# meduZa.net
KiCad netlist of a schematic drawn in EAGLE
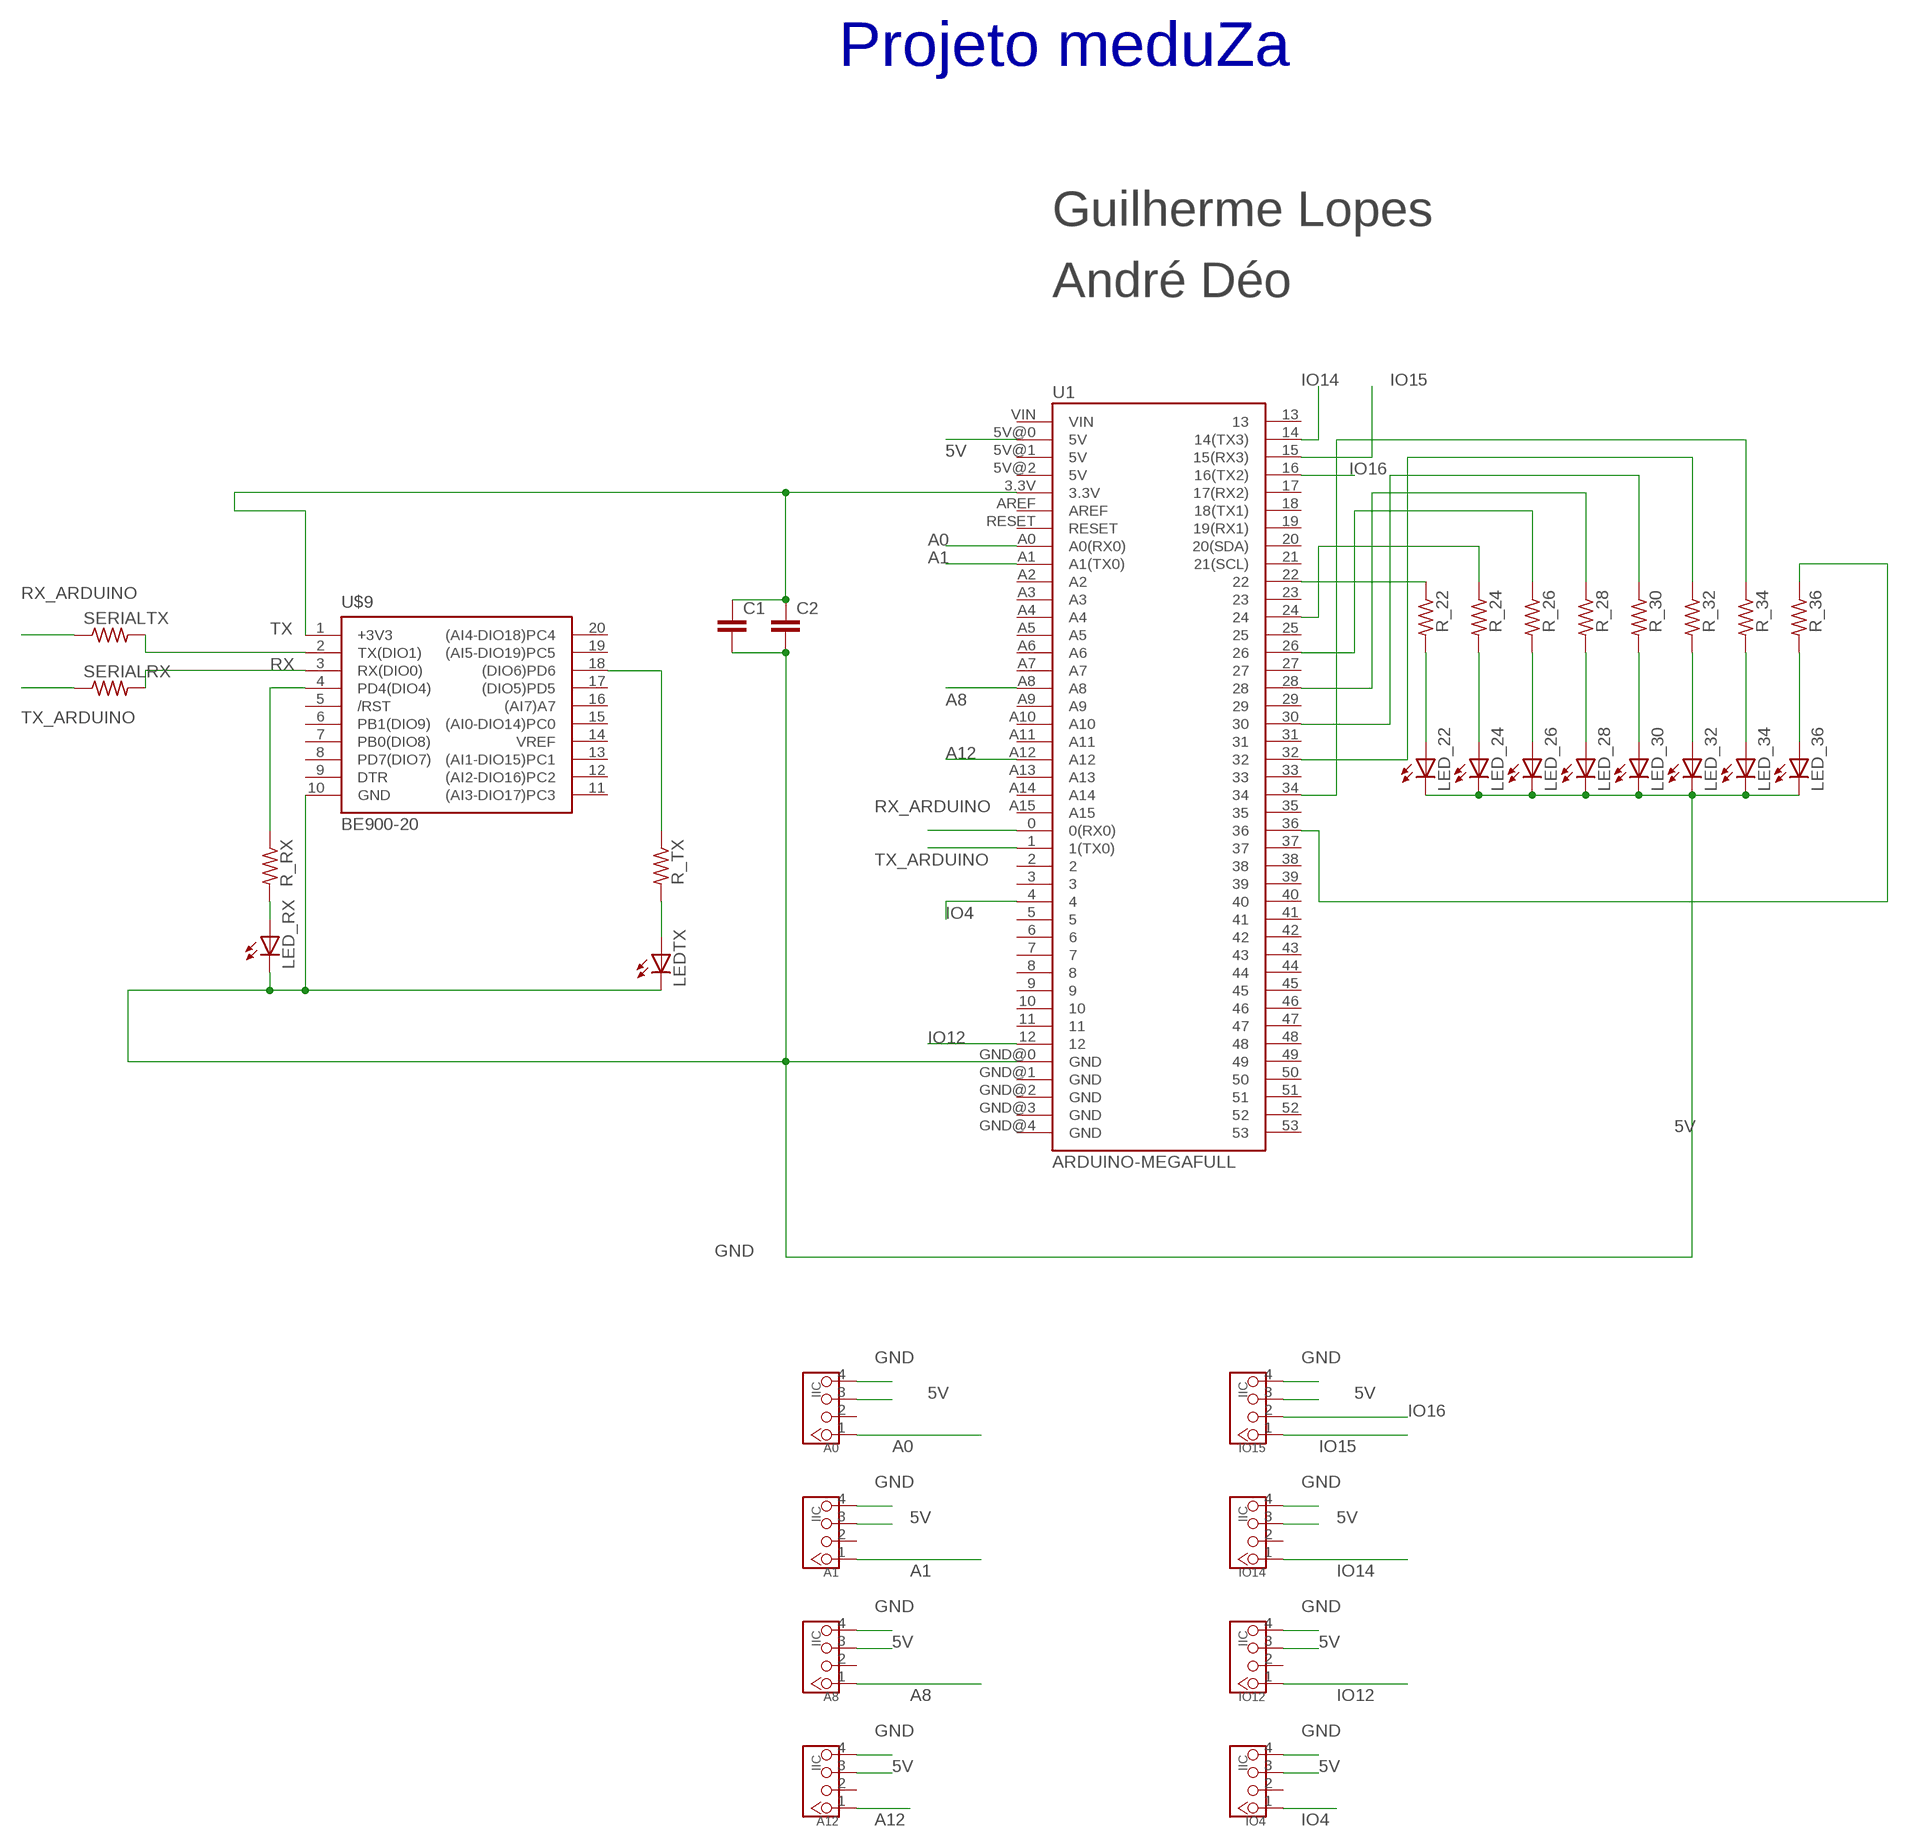
[diagram p0: schematic, sheet 1]

(export (version "E")
  (design (tool "Eeschema 10.0.6"))
  (components
    (comp (ref "A0")
      (value "IIC")
      (footprint "eagle-import:4P-2.0")
      (libsource (lib "eagle-import") (part "TWIG-4P-2.0-2.0"))
    )
    (comp (ref "A1")
      (value "IIC")
      (footprint "eagle-import:4P-2.0")
      (libsource (lib "eagle-import") (part "TWIG-4P-2.0-2.0"))
    )
    (comp (ref "A8")
      (value "IIC")
      (footprint "eagle-import:4P-2.0")
      (libsource (lib "eagle-import") (part "TWIG-4P-2.0-2.0"))
    )
    (comp (ref "A12")
      (value "IIC")
      (footprint "eagle-import:4P-2.0")
      (libsource (lib "eagle-import") (part "TWIG-4P-2.0-2.0"))
    )
    (comp (ref "C1")
      (value "0.1UF-50V-20%(PTH)KIT-EZ")
      (footprint "eagle-import:CAP-PTH-SMALL-KIT")
      (libsource (lib "eagle-import") (part "0.1UF-50V-20%(PTH)KIT-EZ"))
    )
    (comp (ref "C2")
      (value "0.1UF-50V-20%(PTH)KIT-EZ")
      (footprint "eagle-import:CAP-PTH-SMALL-KIT")
      (libsource (lib "eagle-import") (part "0.1UF-50V-20%(PTH)KIT-EZ"))
    )
    (comp (ref "IO4")
      (value "IIC")
      (footprint "eagle-import:4P-2.0")
      (libsource (lib "eagle-import") (part "TWIG-4P-2.0-2.0"))
    )
    (comp (ref "IO12")
      (value "IIC")
      (footprint "eagle-import:4P-2.0")
      (libsource (lib "eagle-import") (part "TWIG-4P-2.0-2.0"))
    )
    (comp (ref "IO14")
      (value "IIC")
      (footprint "eagle-import:4P-2.0")
      (libsource (lib "eagle-import") (part "TWIG-4P-2.0-2.0"))
    )
    (comp (ref "IO15")
      (value "IIC")
      (footprint "eagle-import:4P-2.0")
      (libsource (lib "eagle-import") (part "TWIG-4P-2.0-2.0"))
    )
    (comp (ref "LEDTX")
      (value "LED5MM")
      (footprint "eagle-import:LED5MM")
      (libsource (lib "eagle-import") (part "LED5MM"))
    )
    (comp (ref "LED_22")
      (value "LED5MM")
      (footprint "eagle-import:LED5MM")
      (libsource (lib "eagle-import") (part "LED5MM"))
    )
    (comp (ref "LED_24")
      (value "LED5MM")
      (footprint "eagle-import:LED5MM")
      (libsource (lib "eagle-import") (part "LED5MM"))
    )
    (comp (ref "LED_26")
      (value "LED5MM")
      (footprint "eagle-import:LED5MM")
      (libsource (lib "eagle-import") (part "LED5MM"))
    )
    (comp (ref "LED_28")
      (value "LED5MM")
      (footprint "eagle-import:LED5MM")
      (libsource (lib "eagle-import") (part "LED5MM"))
    )
    (comp (ref "LED_30")
      (value "LED5MM")
      (footprint "eagle-import:LED5MM")
      (libsource (lib "eagle-import") (part "LED5MM"))
    )
    (comp (ref "LED_32")
      (value "LED5MM")
      (footprint "eagle-import:LED5MM")
      (libsource (lib "eagle-import") (part "LED5MM"))
    )
    (comp (ref "LED_34")
      (value "LED5MM")
      (footprint "eagle-import:LED5MM")
      (libsource (lib "eagle-import") (part "LED5MM"))
    )
    (comp (ref "LED_36")
      (value "LED5MM")
      (footprint "eagle-import:LED5MM")
      (libsource (lib "eagle-import") (part "LED5MM"))
    )
    (comp (ref "LED_RX")
      (value "LED5MM")
      (footprint "eagle-import:LED5MM")
      (libsource (lib "eagle-import") (part "LED5MM"))
    )
    (comp (ref "R_22")
      (value "R-US_0204/7")
      (footprint "eagle-import:0204_7")
      (libsource (lib "eagle-import") (part "R-US_0204/7"))
    )
    (comp (ref "R_24")
      (value "R-US_0204/7")
      (footprint "eagle-import:0204_7")
      (libsource (lib "eagle-import") (part "R-US_0204/7"))
    )
    (comp (ref "R_26")
      (value "R-US_0204/7")
      (footprint "eagle-import:0204_7")
      (libsource (lib "eagle-import") (part "R-US_0204/7"))
    )
    (comp (ref "R_28")
      (value "R-US_0204/7")
      (footprint "eagle-import:0204_7")
      (libsource (lib "eagle-import") (part "R-US_0204/7"))
    )
    (comp (ref "R_30")
      (value "R-US_0204/7")
      (footprint "eagle-import:0204_7")
      (libsource (lib "eagle-import") (part "R-US_0204/7"))
    )
    (comp (ref "R_32")
      (value "R-US_0204/7")
      (footprint "eagle-import:0204_7")
      (libsource (lib "eagle-import") (part "R-US_0204/7"))
    )
    (comp (ref "R_34")
      (value "R-US_0204/7")
      (footprint "eagle-import:0204_7")
      (libsource (lib "eagle-import") (part "R-US_0204/7"))
    )
    (comp (ref "R_36")
      (value "R-US_0204/7")
      (footprint "eagle-import:0204_7")
      (libsource (lib "eagle-import") (part "R-US_0204/7"))
    )
    (comp (ref "R_RX")
      (value "R-US_0204/7")
      (footprint "eagle-import:0204_7")
      (libsource (lib "eagle-import") (part "R-US_0204/7"))
    )
    (comp (ref "R_TX")
      (value "R-US_0204/7")
      (footprint "eagle-import:0204_7")
      (libsource (lib "eagle-import") (part "R-US_0204/7"))
    )
    (comp (ref "SERIALRX")
      (value "R-US_0204/7")
      (footprint "eagle-import:0204_7")
      (libsource (lib "eagle-import") (part "R-US_0204/7"))
    )
    (comp (ref "SERIALTX")
      (value "R-US_0204/7")
      (footprint "eagle-import:0204_7")
      (libsource (lib "eagle-import") (part "R-US_0204/7"))
    )
    (comp (ref "U$9")
      (value "BE900-20")
      (footprint "eagle-import:BE900_20")
      (libsource (lib "eagle-import") (part "BE900-20"))
    )
    (comp (ref "U1")
      (value "ARDUINO-MEGAFULL")
      (footprint "eagle-import:ARDUINO_MEGA")
      (libsource (lib "eagle-import") (part "ARDUINO-MEGAFULL"))
    )
  )
  (nets
    (net (code "1") (name "/5V") (class "Default")
      (node (ref "A0") (pin "3") (pinfunction "3_3") (pintype "bidirectional"))
      (node (ref "A1") (pin "3") (pinfunction "3_3") (pintype "bidirectional"))
      (node (ref "A12") (pin "3") (pinfunction "3_3") (pintype "bidirectional"))
      (node (ref "A8") (pin "3") (pinfunction "3_3") (pintype "bidirectional"))
      (node (ref "IO12") (pin "3") (pinfunction "3_3") (pintype "bidirectional"))
      (node (ref "IO14") (pin "3") (pinfunction "3_3") (pintype "bidirectional"))
      (node (ref "IO15") (pin "3") (pinfunction "3_3") (pintype "bidirectional"))
      (node (ref "IO4") (pin "3") (pinfunction "3_3") (pintype "bidirectional"))
      (node (ref "U1") (pin "5V@0") (pinfunction "5V_5V@0") (pintype "bidirectional"))
    )
    (net (code "2") (name "/A0") (class "Default")
      (node (ref "A0") (pin "1") (pinfunction "1_1") (pintype "bidirectional"))
      (node (ref "U1") (pin "A0") (pinfunction "A0(RX0)_A0") (pintype "bidirectional"))
    )
    (net (code "3") (name "/A1") (class "Default")
      (node (ref "A1") (pin "1") (pinfunction "1_1") (pintype "bidirectional"))
      (node (ref "U1") (pin "A1") (pinfunction "A1(TX0)_A1") (pintype "bidirectional"))
    )
    (net (code "4") (name "/A8") (class "Default")
      (node (ref "A8") (pin "1") (pinfunction "1_1") (pintype "bidirectional"))
      (node (ref "U1") (pin "A8") (pinfunction "A8_A8") (pintype "bidirectional"))
    )
    (net (code "5") (name "/A12") (class "Default")
      (node (ref "A12") (pin "1") (pinfunction "1_1") (pintype "bidirectional"))
      (node (ref "U1") (pin "A12") (pinfunction "A12_A12") (pintype "bidirectional"))
    )
    (net (code "6") (name "/GND") (class "Default")
      (node (ref "A0") (pin "4") (pinfunction "4_4") (pintype "bidirectional"))
      (node (ref "A1") (pin "4") (pinfunction "4_4") (pintype "bidirectional"))
      (node (ref "A12") (pin "4") (pinfunction "4_4") (pintype "bidirectional"))
      (node (ref "A8") (pin "4") (pinfunction "4_4") (pintype "bidirectional"))
      (node (ref "C1") (pin "2") (pinfunction "2_2") (pintype "passive"))
      (node (ref "C2") (pin "2") (pinfunction "2_2") (pintype "passive"))
      (node (ref "IO12") (pin "4") (pinfunction "4_4") (pintype "bidirectional"))
      (node (ref "IO14") (pin "4") (pinfunction "4_4") (pintype "bidirectional"))
      (node (ref "IO15") (pin "4") (pinfunction "4_4") (pintype "bidirectional"))
      (node (ref "IO4") (pin "4") (pinfunction "4_4") (pintype "bidirectional"))
      (node (ref "LEDTX") (pin "K") (pinfunction "C_K") (pintype "passive"))
      (node (ref "LED_22") (pin "K") (pinfunction "C_K") (pintype "passive"))
      (node (ref "LED_24") (pin "K") (pinfunction "C_K") (pintype "passive"))
      (node (ref "LED_26") (pin "K") (pinfunction "C_K") (pintype "passive"))
      (node (ref "LED_28") (pin "K") (pinfunction "C_K") (pintype "passive"))
      (node (ref "LED_30") (pin "K") (pinfunction "C_K") (pintype "passive"))
      (node (ref "LED_32") (pin "K") (pinfunction "C_K") (pintype "passive"))
      (node (ref "LED_34") (pin "K") (pinfunction "C_K") (pintype "passive"))
      (node (ref "LED_36") (pin "K") (pinfunction "C_K") (pintype "passive"))
      (node (ref "LED_RX") (pin "K") (pinfunction "C_K") (pintype "passive"))
      (node (ref "U$9") (pin "10") (pinfunction "GND_10") (pintype "power_in"))
      (node (ref "U1") (pin "GND@0") (pinfunction "GND_GND@0") (pintype "bidirectional"))
    )
    (net (code "7") (name "/IO4") (class "Default")
      (node (ref "IO4") (pin "1") (pinfunction "1_1") (pintype "bidirectional"))
      (node (ref "U1") (pin "4") (pinfunction "4_4") (pintype "bidirectional"))
    )
    (net (code "8") (name "/IO12") (class "Default")
      (node (ref "IO12") (pin "1") (pinfunction "1_1") (pintype "bidirectional"))
      (node (ref "U1") (pin "12") (pinfunction "12_12") (pintype "bidirectional"))
    )
    (net (code "9") (name "/IO14") (class "Default")
      (node (ref "IO14") (pin "1") (pinfunction "1_1") (pintype "bidirectional"))
      (node (ref "U1") (pin "14") (pinfunction "14(TX3)_14") (pintype "bidirectional"))
    )
    (net (code "10") (name "/IO15") (class "Default")
      (node (ref "IO15") (pin "1") (pinfunction "1_1") (pintype "bidirectional"))
      (node (ref "U1") (pin "15") (pinfunction "15(RX3)_15") (pintype "bidirectional"))
    )
    (net (code "11") (name "/IO16") (class "Default")
      (node (ref "IO15") (pin "2") (pinfunction "2_2") (pintype "bidirectional"))
      (node (ref "U1") (pin "16") (pinfunction "16(TX2)_16") (pintype "bidirectional"))
    )
    (net (code "12") (name "/RX") (class "Default")
      (node (ref "SERIALRX") (pin "2") (pinfunction "2_2") (pintype "passive"))
      (node (ref "U$9") (pin "3") (pinfunction "RX(DIO0)_3") (pintype "bidirectional"))
    )
    (net (code "13") (name "/RX_ARDUINO") (class "Default")
      (node (ref "SERIALTX") (pin "1") (pinfunction "1_1") (pintype "passive"))
      (node (ref "U1") (pin "0") (pinfunction "0(RX0)_0") (pintype "bidirectional"))
    )
    (net (code "14") (name "/TX") (class "Default")
      (node (ref "SERIALTX") (pin "2") (pinfunction "2_2") (pintype "passive"))
      (node (ref "U$9") (pin "2") (pinfunction "TX(DIO1)_2") (pintype "bidirectional"))
    )
    (net (code "15") (name "/TX_ARDUINO") (class "Default")
      (node (ref "SERIALRX") (pin "1") (pinfunction "1_1") (pintype "passive"))
      (node (ref "U1") (pin "1") (pinfunction "1(TX0)_1") (pintype "bidirectional"))
    )
    (net (code "16") (name "Net-(LEDTX-PadA)") (class "Default")
      (node (ref "LEDTX") (pin "A") (pinfunction "A_A") (pintype "passive"))
      (node (ref "R_TX") (pin "2") (pinfunction "2_2") (pintype "passive"))
    )
    (net (code "17") (name "Net-(LED_22-PadA)") (class "Default")
      (node (ref "LED_22") (pin "A") (pinfunction "A_A") (pintype "passive"))
      (node (ref "R_22") (pin "2") (pinfunction "2_2") (pintype "passive"))
    )
    (net (code "18") (name "Net-(LED_24-PadA)") (class "Default")
      (node (ref "LED_24") (pin "A") (pinfunction "A_A") (pintype "passive"))
      (node (ref "R_24") (pin "2") (pinfunction "2_2") (pintype "passive"))
    )
    (net (code "19") (name "Net-(LED_26-PadA)") (class "Default")
      (node (ref "LED_26") (pin "A") (pinfunction "A_A") (pintype "passive"))
      (node (ref "R_26") (pin "2") (pinfunction "2_2") (pintype "passive"))
    )
    (net (code "20") (name "Net-(LED_28-PadA)") (class "Default")
      (node (ref "LED_28") (pin "A") (pinfunction "A_A") (pintype "passive"))
      (node (ref "R_28") (pin "2") (pinfunction "2_2") (pintype "passive"))
    )
    (net (code "21") (name "Net-(LED_30-PadA)") (class "Default")
      (node (ref "LED_30") (pin "A") (pinfunction "A_A") (pintype "passive"))
      (node (ref "R_30") (pin "2") (pinfunction "2_2") (pintype "passive"))
    )
    (net (code "22") (name "Net-(LED_32-PadA)") (class "Default")
      (node (ref "LED_32") (pin "A") (pinfunction "A_A") (pintype "passive"))
      (node (ref "R_32") (pin "2") (pinfunction "2_2") (pintype "passive"))
    )
    (net (code "23") (name "Net-(LED_34-PadA)") (class "Default")
      (node (ref "LED_34") (pin "A") (pinfunction "A_A") (pintype "passive"))
      (node (ref "R_34") (pin "2") (pinfunction "2_2") (pintype "passive"))
    )
    (net (code "24") (name "Net-(LED_36-PadA)") (class "Default")
      (node (ref "LED_36") (pin "A") (pinfunction "A_A") (pintype "passive"))
      (node (ref "R_36") (pin "2") (pinfunction "2_2") (pintype "passive"))
    )
    (net (code "25") (name "Net-(LED_RX-PadA)") (class "Default")
      (node (ref "LED_RX") (pin "A") (pinfunction "A_A") (pintype "passive"))
      (node (ref "R_RX") (pin "2") (pinfunction "2_2") (pintype "passive"))
    )
    (net (code "26") (name "Net-(R_22-Pad1)") (class "Default")
      (node (ref "R_22") (pin "1") (pinfunction "1_1") (pintype "passive"))
      (node (ref "U1") (pin "22") (pinfunction "22_22") (pintype "bidirectional"))
    )
    (net (code "27") (name "Net-(R_24-Pad1)") (class "Default")
      (node (ref "R_24") (pin "1") (pinfunction "1_1") (pintype "passive"))
      (node (ref "U1") (pin "24") (pinfunction "24_24") (pintype "bidirectional"))
    )
    (net (code "28") (name "Net-(R_26-Pad1)") (class "Default")
      (node (ref "R_26") (pin "1") (pinfunction "1_1") (pintype "passive"))
      (node (ref "U1") (pin "26") (pinfunction "26_26") (pintype "bidirectional"))
    )
    (net (code "29") (name "Net-(R_28-Pad1)") (class "Default")
      (node (ref "R_28") (pin "1") (pinfunction "1_1") (pintype "passive"))
      (node (ref "U1") (pin "28") (pinfunction "28_28") (pintype "bidirectional"))
    )
    (net (code "30") (name "Net-(R_30-Pad1)") (class "Default")
      (node (ref "R_30") (pin "1") (pinfunction "1_1") (pintype "passive"))
      (node (ref "U1") (pin "30") (pinfunction "30_30") (pintype "bidirectional"))
    )
    (net (code "31") (name "Net-(R_32-Pad1)") (class "Default")
      (node (ref "R_32") (pin "1") (pinfunction "1_1") (pintype "passive"))
      (node (ref "U1") (pin "32") (pinfunction "32_32") (pintype "bidirectional"))
    )
    (net (code "32") (name "Net-(R_34-Pad1)") (class "Default")
      (node (ref "R_34") (pin "1") (pinfunction "1_1") (pintype "passive"))
      (node (ref "U1") (pin "34") (pinfunction "34_34") (pintype "bidirectional"))
    )
    (net (code "33") (name "Net-(R_36-Pad1)") (class "Default")
      (node (ref "R_36") (pin "1") (pinfunction "1_1") (pintype "passive"))
      (node (ref "U1") (pin "36") (pinfunction "36_36") (pintype "bidirectional"))
    )
    (net (code "34") (name "Net-(U$9-(DIO6)PD6)") (class "Default")
      (node (ref "R_TX") (pin "1") (pinfunction "1_1") (pintype "passive"))
      (node (ref "U$9") (pin "18") (pinfunction "(DIO6)PD6_18") (pintype "bidirectional"))
    )
    (net (code "35") (name "Net-(U$9-+3V3)") (class "Default")
      (node (ref "C1") (pin "1") (pinfunction "1_1") (pintype "passive"))
      (node (ref "C2") (pin "1") (pinfunction "1_1") (pintype "passive"))
      (node (ref "U$9") (pin "1") (pinfunction "+3V3_1") (pintype "power_in"))
      (node (ref "U1") (pin "3.3V") (pinfunction "3.3V_3.3V") (pintype "bidirectional"))
    )
    (net (code "36") (name "Net-(U$9-PD4(DIO4))") (class "Default")
      (node (ref "R_RX") (pin "1") (pinfunction "1_1") (pintype "passive"))
      (node (ref "U$9") (pin "4") (pinfunction "PD4(DIO4)_4") (pintype "bidirectional"))
    )
    (net (code "37") (name "unconnected-(A0-Pad2)") (class "Default")
      (node (ref "A0") (pin "2") (pinfunction "2_2") (pintype "bidirectional"))
    )
    (net (code "38") (name "unconnected-(A1-Pad2)") (class "Default")
      (node (ref "A1") (pin "2") (pinfunction "2_2") (pintype "bidirectional"))
    )
    (net (code "39") (name "unconnected-(A8-Pad2)") (class "Default")
      (node (ref "A8") (pin "2") (pinfunction "2_2") (pintype "bidirectional"))
    )
    (net (code "40") (name "unconnected-(A12-Pad2)") (class "Default")
      (node (ref "A12") (pin "2") (pinfunction "2_2") (pintype "bidirectional"))
    )
    (net (code "41") (name "unconnected-(IO4-Pad2)") (class "Default")
      (node (ref "IO4") (pin "2") (pinfunction "2_2") (pintype "bidirectional"))
    )
    (net (code "42") (name "unconnected-(IO12-Pad2)") (class "Default")
      (node (ref "IO12") (pin "2") (pinfunction "2_2") (pintype "bidirectional"))
    )
    (net (code "43") (name "unconnected-(IO14-Pad2)") (class "Default")
      (node (ref "IO14") (pin "2") (pinfunction "2_2") (pintype "bidirectional"))
    )
    (net (code "44") (name "unconnected-(U$9-(AI0-DIO14)PC0-Pad15)") (class "Default")
      (node (ref "U$9") (pin "15") (pinfunction "(AI0-DIO14)PC0_15") (pintype "bidirectional"))
    )
    (net (code "45") (name "unconnected-(U$9-(AI1-DIO15)PC1-Pad13)") (class "Default")
      (node (ref "U$9") (pin "13") (pinfunction "(AI1-DIO15)PC1_13") (pintype "bidirectional"))
    )
    (net (code "46") (name "unconnected-(U$9-(AI2-DIO16)PC2-Pad12)") (class "Default")
      (node (ref "U$9") (pin "12") (pinfunction "(AI2-DIO16)PC2_12") (pintype "bidirectional"))
    )
    (net (code "47") (name "unconnected-(U$9-(AI3-DIO17)PC3-Pad11)") (class "Default")
      (node (ref "U$9") (pin "11") (pinfunction "(AI3-DIO17)PC3_11") (pintype "bidirectional"))
    )
    (net (code "48") (name "unconnected-(U$9-(AI4-DIO18)PC4-Pad20)") (class "Default")
      (node (ref "U$9") (pin "20") (pinfunction "(AI4-DIO18)PC4_20") (pintype "bidirectional"))
    )
    (net (code "49") (name "unconnected-(U$9-(AI5-DIO19)PC5-Pad19)") (class "Default")
      (node (ref "U$9") (pin "19") (pinfunction "(AI5-DIO19)PC5_19") (pintype "bidirectional"))
    )
    (net (code "50") (name "unconnected-(U$9-(AI7)A7-Pad16)") (class "Default")
      (node (ref "U$9") (pin "16") (pinfunction "(AI7)A7_16") (pintype "bidirectional"))
    )
    (net (code "51") (name "unconnected-(U$9-(DIO5)PD5-Pad17)") (class "Default")
      (node (ref "U$9") (pin "17") (pinfunction "(DIO5)PD5_17") (pintype "bidirectional"))
    )
    (net (code "52") (name "unconnected-(U$9-DTR-Pad9)") (class "Default")
      (node (ref "U$9") (pin "9") (pinfunction "DTR_9") (pintype "bidirectional"))
    )
    (net (code "53") (name "unconnected-(U$9-PB0(DIO8)-Pad7)") (class "Default")
      (node (ref "U$9") (pin "7") (pinfunction "PB0(DIO8)_7") (pintype "bidirectional"))
    )
    (net (code "54") (name "unconnected-(U$9-PB1(DIO9)-Pad6)") (class "Default")
      (node (ref "U$9") (pin "6") (pinfunction "PB1(DIO9)_6") (pintype "bidirectional"))
    )
    (net (code "55") (name "unconnected-(U$9-PD7(DIO7)-Pad8)") (class "Default")
      (node (ref "U$9") (pin "8") (pinfunction "PD7(DIO7)_8") (pintype "bidirectional"))
    )
    (net (code "56") (name "unconnected-(U$9-VREF-Pad14)") (class "Default")
      (node (ref "U$9") (pin "14") (pinfunction "VREF_14") (pintype "bidirectional"))
    )
    (net (code "57") (name "unconnected-(U$9-{slash}RST-Pad5)") (class "Default")
      (node (ref "U$9") (pin "5") (pinfunction "/RST_5") (pintype "bidirectional"))
    )
    (net (code "58") (name "unconnected-(U1-5V-Pad5V@1)") (class "Default")
      (node (ref "U1") (pin "5V@1") (pinfunction "5V_5V@1") (pintype "bidirectional"))
    )
    (net (code "59") (name "unconnected-(U1-5V-Pad5V@2)") (class "Default")
      (node (ref "U1") (pin "5V@2") (pinfunction "5V_5V@2") (pintype "bidirectional"))
    )
    (net (code "60") (name "unconnected-(U1-17(RX2)-Pad17)") (class "Default")
      (node (ref "U1") (pin "17") (pinfunction "17(RX2)_17") (pintype "bidirectional"))
    )
    (net (code "61") (name "unconnected-(U1-18(TX1)-Pad18)") (class "Default")
      (node (ref "U1") (pin "18") (pinfunction "18(TX1)_18") (pintype "bidirectional"))
    )
    (net (code "62") (name "unconnected-(U1-19(RX1)-Pad19)") (class "Default")
      (node (ref "U1") (pin "19") (pinfunction "19(RX1)_19") (pintype "bidirectional"))
    )
    (net (code "63") (name "unconnected-(U1-20(SDA)-Pad20)") (class "Default")
      (node (ref "U1") (pin "20") (pinfunction "20(SDA)_20") (pintype "bidirectional"))
    )
    (net (code "64") (name "unconnected-(U1-21(SCL)-Pad21)") (class "Default")
      (node (ref "U1") (pin "21") (pinfunction "21(SCL)_21") (pintype "bidirectional"))
    )
    (net (code "65") (name "unconnected-(U1-GND-PadGND@1)") (class "Default")
      (node (ref "U1") (pin "GND@1") (pinfunction "GND_GND@1") (pintype "bidirectional"))
    )
    (net (code "66") (name "unconnected-(U1-GND-PadGND@2)") (class "Default")
      (node (ref "U1") (pin "GND@2") (pinfunction "GND_GND@2") (pintype "bidirectional"))
    )
    (net (code "67") (name "unconnected-(U1-GND-PadGND@3)") (class "Default")
      (node (ref "U1") (pin "GND@3") (pinfunction "GND_GND@3") (pintype "bidirectional"))
    )
    (net (code "68") (name "unconnected-(U1-GND-PadGND@4)") (class "Default")
      (node (ref "U1") (pin "GND@4") (pinfunction "GND_GND@4") (pintype "bidirectional"))
    )
    (net (code "69") (name "unconnected-(U1-Pad2)") (class "Default")
      (node (ref "U1") (pin "2") (pinfunction "2_2") (pintype "bidirectional"))
    )
    (net (code "70") (name "unconnected-(U1-Pad3)") (class "Default")
      (node (ref "U1") (pin "3") (pinfunction "3_3") (pintype "bidirectional"))
    )
    (net (code "71") (name "unconnected-(U1-Pad5)") (class "Default")
      (node (ref "U1") (pin "5") (pinfunction "5_5") (pintype "bidirectional"))
    )
    (net (code "72") (name "unconnected-(U1-Pad6)") (class "Default")
      (node (ref "U1") (pin "6") (pinfunction "6_6") (pintype "bidirectional"))
    )
    (net (code "73") (name "unconnected-(U1-Pad7)") (class "Default")
      (node (ref "U1") (pin "7") (pinfunction "7_7") (pintype "bidirectional"))
    )
    (net (code "74") (name "unconnected-(U1-Pad8)") (class "Default")
      (node (ref "U1") (pin "8") (pinfunction "8_8") (pintype "bidirectional"))
    )
    (net (code "75") (name "unconnected-(U1-Pad9)") (class "Default")
      (node (ref "U1") (pin "9") (pinfunction "9_9") (pintype "bidirectional"))
    )
    (net (code "76") (name "unconnected-(U1-Pad10)") (class "Default")
      (node (ref "U1") (pin "10") (pinfunction "10_10") (pintype "bidirectional"))
    )
    (net (code "77") (name "unconnected-(U1-Pad11)") (class "Default")
      (node (ref "U1") (pin "11") (pinfunction "11_11") (pintype "bidirectional"))
    )
    (net (code "78") (name "unconnected-(U1-Pad13)") (class "Default")
      (node (ref "U1") (pin "13") (pinfunction "13_13") (pintype "bidirectional"))
    )
    (net (code "79") (name "unconnected-(U1-Pad23)") (class "Default")
      (node (ref "U1") (pin "23") (pinfunction "23_23") (pintype "bidirectional"))
    )
    (net (code "80") (name "unconnected-(U1-Pad25)") (class "Default")
      (node (ref "U1") (pin "25") (pinfunction "25_25") (pintype "bidirectional"))
    )
    (net (code "81") (name "unconnected-(U1-Pad27)") (class "Default")
      (node (ref "U1") (pin "27") (pinfunction "27_27") (pintype "bidirectional"))
    )
    (net (code "82") (name "unconnected-(U1-Pad29)") (class "Default")
      (node (ref "U1") (pin "29") (pinfunction "29_29") (pintype "bidirectional"))
    )
    (net (code "83") (name "unconnected-(U1-Pad31)") (class "Default")
      (node (ref "U1") (pin "31") (pinfunction "31_31") (pintype "bidirectional"))
    )
    (net (code "84") (name "unconnected-(U1-Pad33)") (class "Default")
      (node (ref "U1") (pin "33") (pinfunction "33_33") (pintype "bidirectional"))
    )
    (net (code "85") (name "unconnected-(U1-Pad35)") (class "Default")
      (node (ref "U1") (pin "35") (pinfunction "35_35") (pintype "bidirectional"))
    )
    (net (code "86") (name "unconnected-(U1-Pad37)") (class "Default")
      (node (ref "U1") (pin "37") (pinfunction "37_37") (pintype "bidirectional"))
    )
    (net (code "87") (name "unconnected-(U1-Pad38)") (class "Default")
      (node (ref "U1") (pin "38") (pinfunction "38_38") (pintype "bidirectional"))
    )
    (net (code "88") (name "unconnected-(U1-Pad39)") (class "Default")
      (node (ref "U1") (pin "39") (pinfunction "39_39") (pintype "bidirectional"))
    )
    (net (code "89") (name "unconnected-(U1-Pad40)") (class "Default")
      (node (ref "U1") (pin "40") (pinfunction "40_40") (pintype "bidirectional"))
    )
    (net (code "90") (name "unconnected-(U1-Pad41)") (class "Default")
      (node (ref "U1") (pin "41") (pinfunction "41_41") (pintype "bidirectional"))
    )
    (net (code "91") (name "unconnected-(U1-Pad42)") (class "Default")
      (node (ref "U1") (pin "42") (pinfunction "42_42") (pintype "bidirectional"))
    )
    (net (code "92") (name "unconnected-(U1-Pad43)") (class "Default")
      (node (ref "U1") (pin "43") (pinfunction "43_43") (pintype "bidirectional"))
    )
    (net (code "93") (name "unconnected-(U1-Pad44)") (class "Default")
      (node (ref "U1") (pin "44") (pinfunction "44_44") (pintype "bidirectional"))
    )
    (net (code "94") (name "unconnected-(U1-Pad45)") (class "Default")
      (node (ref "U1") (pin "45") (pinfunction "45_45") (pintype "bidirectional"))
    )
    (net (code "95") (name "unconnected-(U1-Pad46)") (class "Default")
      (node (ref "U1") (pin "46") (pinfunction "46_46") (pintype "bidirectional"))
    )
    (net (code "96") (name "unconnected-(U1-Pad47)") (class "Default")
      (node (ref "U1") (pin "47") (pinfunction "47_47") (pintype "bidirectional"))
    )
    (net (code "97") (name "unconnected-(U1-Pad48)") (class "Default")
      (node (ref "U1") (pin "48") (pinfunction "48_48") (pintype "bidirectional"))
    )
    (net (code "98") (name "unconnected-(U1-Pad49)") (class "Default")
      (node (ref "U1") (pin "49") (pinfunction "49_49") (pintype "bidirectional"))
    )
    (net (code "99") (name "unconnected-(U1-Pad50)") (class "Default")
      (node (ref "U1") (pin "50") (pinfunction "50_50") (pintype "bidirectional"))
    )
    (net (code "100") (name "unconnected-(U1-Pad51)") (class "Default")
      (node (ref "U1") (pin "51") (pinfunction "51_51") (pintype "bidirectional"))
    )
    (net (code "101") (name "unconnected-(U1-Pad52)") (class "Default")
      (node (ref "U1") (pin "52") (pinfunction "52_52") (pintype "bidirectional"))
    )
    (net (code "102") (name "unconnected-(U1-Pad53)") (class "Default")
      (node (ref "U1") (pin "53") (pinfunction "53_53") (pintype "bidirectional"))
    )
    (net (code "103") (name "unconnected-(U1-PadA2)") (class "Default")
      (node (ref "U1") (pin "A2") (pinfunction "A2_A2") (pintype "bidirectional"))
    )
    (net (code "104") (name "unconnected-(U1-PadA3)") (class "Default")
      (node (ref "U1") (pin "A3") (pinfunction "A3_A3") (pintype "bidirectional"))
    )
    (net (code "105") (name "unconnected-(U1-PadA4)") (class "Default")
      (node (ref "U1") (pin "A4") (pinfunction "A4_A4") (pintype "bidirectional"))
    )
    (net (code "106") (name "unconnected-(U1-PadA5)") (class "Default")
      (node (ref "U1") (pin "A5") (pinfunction "A5_A5") (pintype "bidirectional"))
    )
    (net (code "107") (name "unconnected-(U1-PadA6)") (class "Default")
      (node (ref "U1") (pin "A6") (pinfunction "A6_A6") (pintype "bidirectional"))
    )
    (net (code "108") (name "unconnected-(U1-PadA7)") (class "Default")
      (node (ref "U1") (pin "A7") (pinfunction "A7_A7") (pintype "bidirectional"))
    )
    (net (code "109") (name "unconnected-(U1-PadA9)") (class "Default")
      (node (ref "U1") (pin "A9") (pinfunction "A9_A9") (pintype "bidirectional"))
    )
    (net (code "110") (name "unconnected-(U1-PadA10)") (class "Default")
      (node (ref "U1") (pin "A10") (pinfunction "A10_A10") (pintype "bidirectional"))
    )
    (net (code "111") (name "unconnected-(U1-PadA11)") (class "Default")
      (node (ref "U1") (pin "A11") (pinfunction "A11_A11") (pintype "bidirectional"))
    )
    (net (code "112") (name "unconnected-(U1-PadA13)") (class "Default")
      (node (ref "U1") (pin "A13") (pinfunction "A13_A13") (pintype "bidirectional"))
    )
    (net (code "113") (name "unconnected-(U1-PadA14)") (class "Default")
      (node (ref "U1") (pin "A14") (pinfunction "A14_A14") (pintype "bidirectional"))
    )
    (net (code "114") (name "unconnected-(U1-PadA15)") (class "Default")
      (node (ref "U1") (pin "A15") (pinfunction "A15_A15") (pintype "bidirectional"))
    )
    (net (code "115") (name "unconnected-(U1-PadAREF)") (class "Default")
      (node (ref "U1") (pin "AREF") (pinfunction "AREF_AREF") (pintype "bidirectional"))
    )
    (net (code "116") (name "unconnected-(U1-PadRESET)") (class "Default")
      (node (ref "U1") (pin "RESET") (pinfunction "RESET_RESET") (pintype "bidirectional"))
    )
    (net (code "117") (name "unconnected-(U1-PadVIN)") (class "Default")
      (node (ref "U1") (pin "VIN") (pinfunction "VIN_VIN") (pintype "bidirectional"))
    )
  )
)
